# esp-pinlet.net
KiCad netlist of a schematic drawn in EAGLE
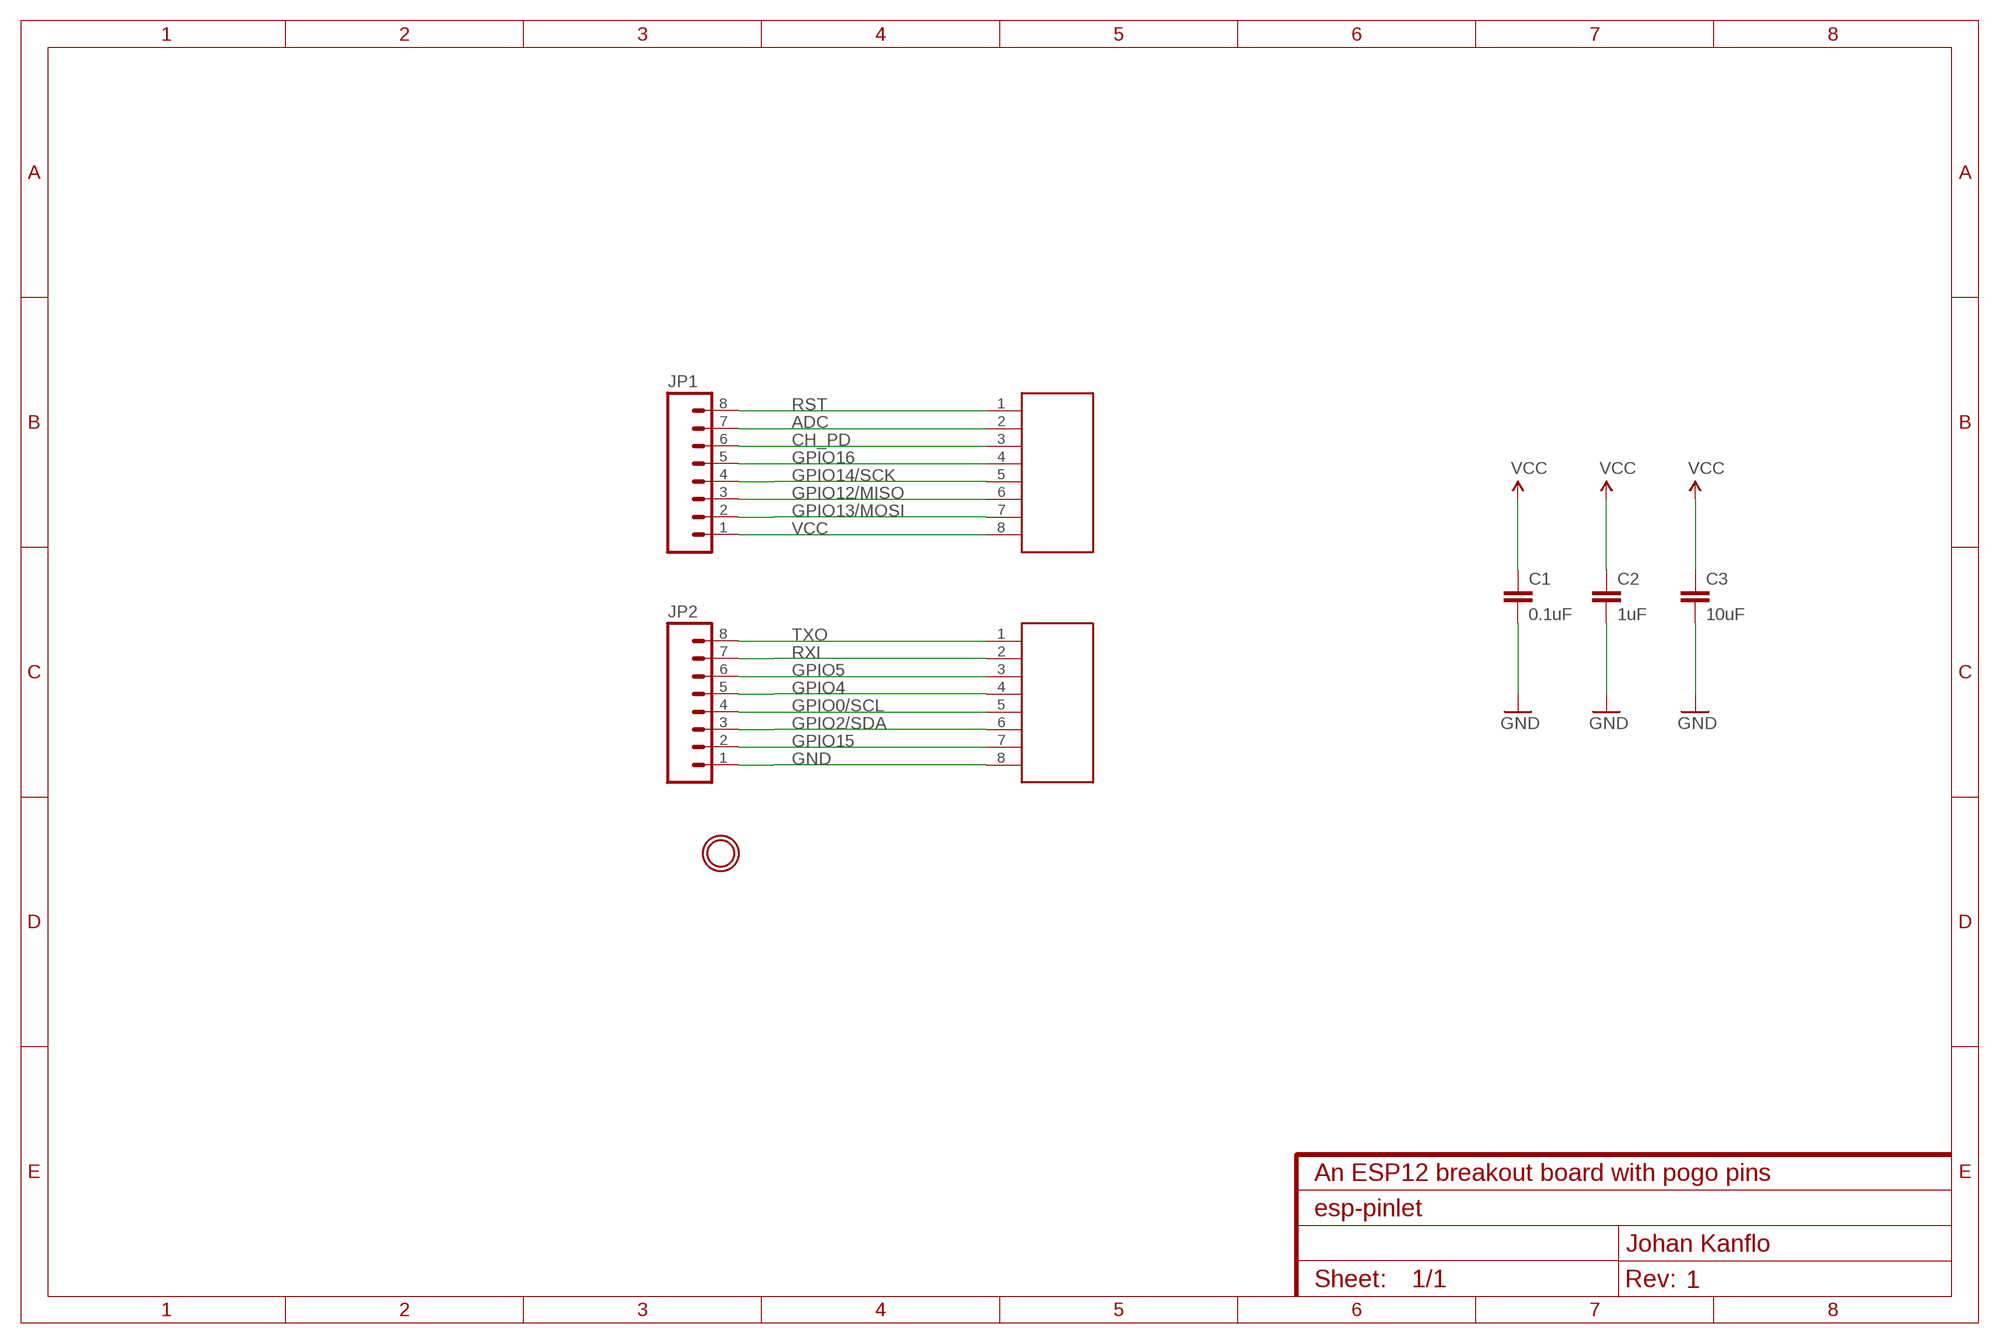
[diagram p0: schematic, sheet 1]

(export (version "E")
  (design (tool "Eeschema 10.0.6"))
  (components
    (comp (ref "C1")
      (value "0.1uF")
      (footprint "eagle-import:0603-CAP")
      (libsource (lib "eagle-import") (part "CAP0603-CAP"))
    )
    (comp (ref "C2")
      (value "1uF")
      (footprint "eagle-import:0603-CAP")
      (libsource (lib "eagle-import") (part "CAP0603-CAP"))
    )
    (comp (ref "C3")
      (value "10uF")
      (footprint "eagle-import:0603-CAP")
      (libsource (lib "eagle-import") (part "CAP0603-CAP"))
    )
    (comp (ref "JP1")
      (value "M08")
      (footprint "eagle-import:1X08_ROUND")
      (libsource (lib "eagle-import") (part "M08"))
    )
    (comp (ref "JP2")
      (value "M08")
      (footprint "eagle-import:1X08_ROUND")
      (libsource (lib "eagle-import") (part "M08"))
    )
    (comp (ref "U$2")
      (value "82XMM_POGO_PIN")
      (footprint "eagle-import:8X2MM_POGO_PIN")
      (libsource (lib "eagle-import") (part "82XMM_POGO_PIN"))
    )
    (comp (ref "U$3")
      (value "82XMM_POGO_PIN")
      (footprint "eagle-import:8X2MM_POGO_PIN")
      (libsource (lib "eagle-import") (part "82XMM_POGO_PIN"))
    )
    (comp (ref "U$6")
      (value "MOUNTINGHOLE2.0")
      (footprint "eagle-import:MOUNTINGHOLE_2.0_PLATED")
      (libsource (lib "eagle-import") (part "MOUNTINGHOLE2.0"))
    )
  )
  (nets
    (net (code "1") (name "/ADC") (class "Default")
      (node (ref "JP1") (pin "7") (pinfunction "7_7") (pintype "passive"))
      (node (ref "U$2") (pin "2") (pinfunction "2_2") (pintype "bidirectional"))
    )
    (net (code "2") (name "/CH_PD") (class "Default")
      (node (ref "JP1") (pin "6") (pinfunction "6_6") (pintype "passive"))
      (node (ref "U$2") (pin "3") (pinfunction "3_3") (pintype "bidirectional"))
    )
    (net (code "3") (name "/GPIO0{slash}SCL") (class "Default")
      (node (ref "JP2") (pin "4") (pinfunction "4_4") (pintype "passive"))
      (node (ref "U$3") (pin "5") (pinfunction "5_5") (pintype "bidirectional"))
    )
    (net (code "4") (name "/GPIO2{slash}SDA") (class "Default")
      (node (ref "JP2") (pin "3") (pinfunction "3_3") (pintype "passive"))
      (node (ref "U$3") (pin "6") (pinfunction "6_6") (pintype "bidirectional"))
    )
    (net (code "5") (name "/GPIO4") (class "Default")
      (node (ref "JP2") (pin "5") (pinfunction "5_5") (pintype "passive"))
      (node (ref "U$3") (pin "4") (pinfunction "4_4") (pintype "bidirectional"))
    )
    (net (code "6") (name "/GPIO5") (class "Default")
      (node (ref "JP2") (pin "6") (pinfunction "6_6") (pintype "passive"))
      (node (ref "U$3") (pin "3") (pinfunction "3_3") (pintype "bidirectional"))
    )
    (net (code "7") (name "/GPIO12{slash}MISO") (class "Default")
      (node (ref "JP1") (pin "3") (pinfunction "3_3") (pintype "passive"))
      (node (ref "U$2") (pin "6") (pinfunction "6_6") (pintype "bidirectional"))
    )
    (net (code "8") (name "/GPIO13{slash}MOSI") (class "Default")
      (node (ref "JP1") (pin "2") (pinfunction "2_2") (pintype "passive"))
      (node (ref "U$2") (pin "7") (pinfunction "7_7") (pintype "bidirectional"))
    )
    (net (code "9") (name "/GPIO14{slash}SCK") (class "Default")
      (node (ref "JP1") (pin "4") (pinfunction "4_4") (pintype "passive"))
      (node (ref "U$2") (pin "5") (pinfunction "5_5") (pintype "bidirectional"))
    )
    (net (code "10") (name "/GPIO15") (class "Default")
      (node (ref "JP2") (pin "2") (pinfunction "2_2") (pintype "passive"))
      (node (ref "U$3") (pin "7") (pinfunction "7_7") (pintype "bidirectional"))
    )
    (net (code "11") (name "/GPIO16") (class "Default")
      (node (ref "JP1") (pin "5") (pinfunction "5_5") (pintype "passive"))
      (node (ref "U$2") (pin "4") (pinfunction "4_4") (pintype "bidirectional"))
    )
    (net (code "12") (name "/RST") (class "Default")
      (node (ref "JP1") (pin "8") (pinfunction "8_8") (pintype "passive"))
      (node (ref "U$2") (pin "1") (pinfunction "1_1") (pintype "bidirectional"))
    )
    (net (code "13") (name "/RXI") (class "Default")
      (node (ref "JP2") (pin "7") (pinfunction "7_7") (pintype "passive"))
      (node (ref "U$3") (pin "2") (pinfunction "2_2") (pintype "bidirectional"))
    )
    (net (code "14") (name "/TXO") (class "Default")
      (node (ref "JP2") (pin "8") (pinfunction "8_8") (pintype "passive"))
      (node (ref "U$3") (pin "1") (pinfunction "1_1") (pintype "bidirectional"))
    )
    (net (code "15") (name "GND") (class "Default")
      (node (ref "C1") (pin "2") (pinfunction "2_2") (pintype "passive"))
      (node (ref "C2") (pin "2") (pinfunction "2_2") (pintype "passive"))
      (node (ref "C3") (pin "2") (pinfunction "2_2") (pintype "passive"))
      (node (ref "JP2") (pin "1") (pinfunction "1_1") (pintype "passive"))
      (node (ref "U$3") (pin "8") (pinfunction "8_8") (pintype "bidirectional"))
    )
    (net (code "16") (name "VCC") (class "Default")
      (node (ref "C1") (pin "1") (pinfunction "1_1") (pintype "passive"))
      (node (ref "C2") (pin "1") (pinfunction "1_1") (pintype "passive"))
      (node (ref "C3") (pin "1") (pinfunction "1_1") (pintype "passive"))
      (node (ref "JP1") (pin "1") (pinfunction "1_1") (pintype "passive"))
      (node (ref "U$2") (pin "8") (pinfunction "8_8") (pintype "bidirectional"))
    )
  )
)
